# DCF_ALIM_SWITCH_RESET.net
KiCad netlist of a schematic drawn in Altium Designer
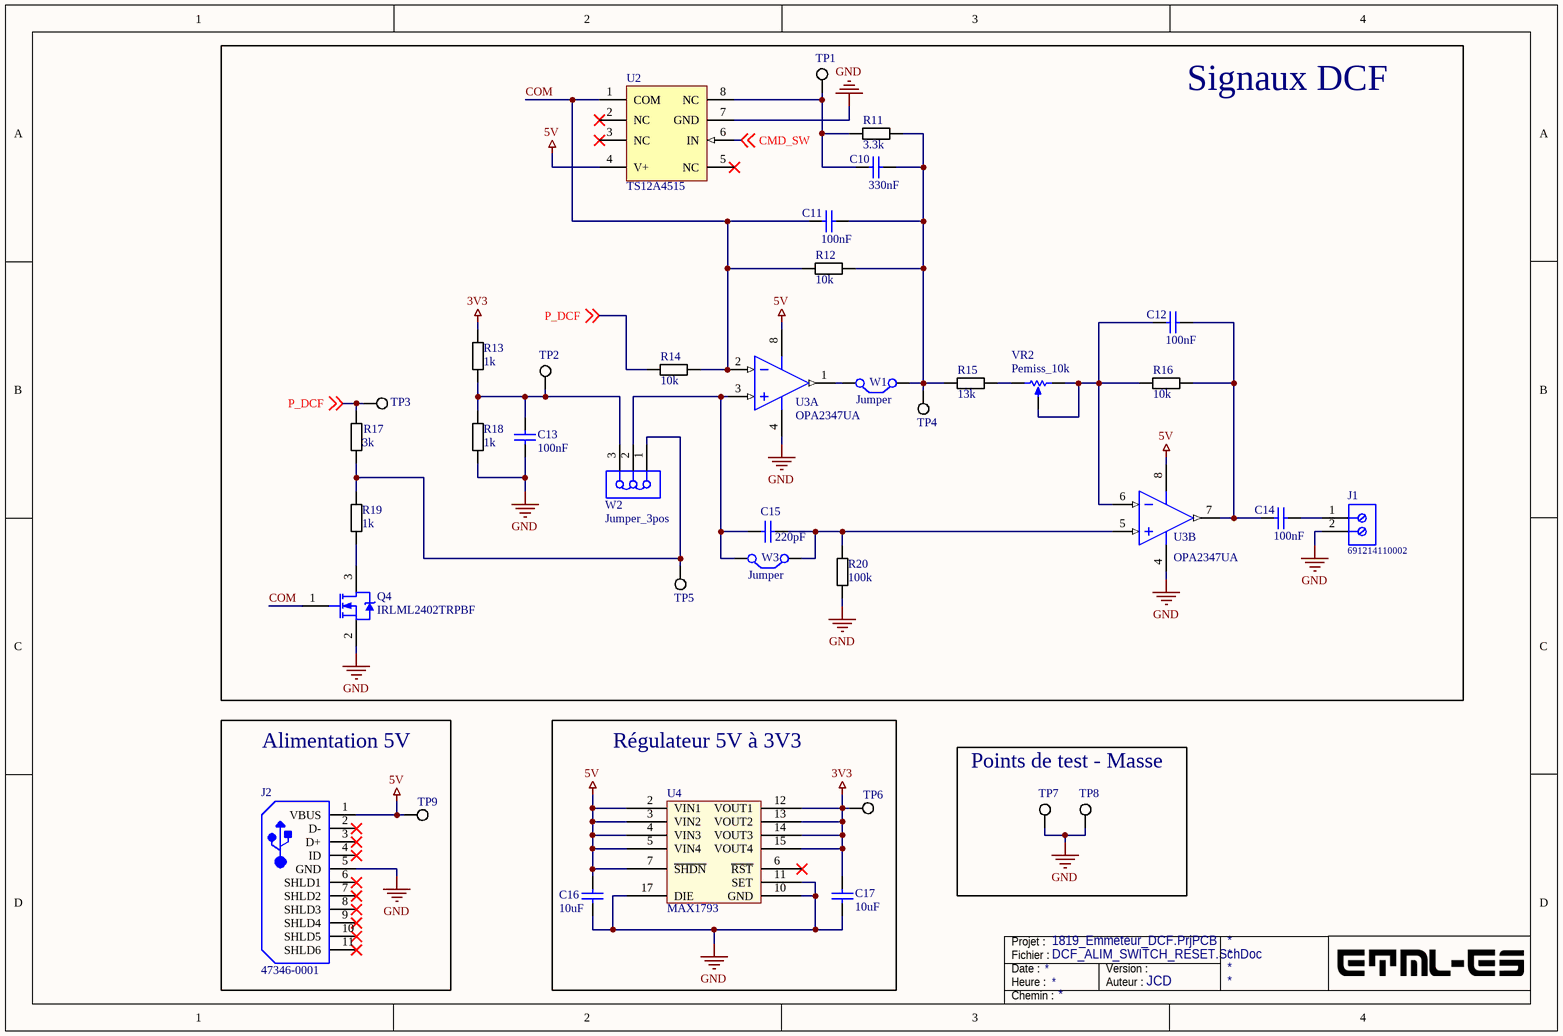
[diagram p0: DCF_ALIM_SWITCH_RESET.SchDoc]

(export (version "E")
  (design (tool "Eeschema 10.0.6"))
  (components
    (comp (ref "C10")
      (value "330nF")
      (footprint "C0805")
      (description "Capacitor")
      (fields (field (name "PUBLISHER") "Altium Limited"))
      (libsource (lib "Miscellaneous Devices") (part "Cap"))
    )
    (comp (ref "C11")
      (value "100nF")
      (footprint "C0805")
      (description "Capacitor")
      (fields (field (name "PUBLISHER") "Altium Limited"))
      (libsource (lib "Miscellaneous Devices") (part "Cap"))
    )
    (comp (ref "C12")
      (value "100nF")
      (footprint "C0805")
      (description "Capacitor")
      (fields (field (name "PUBLISHER") "Altium Limited"))
      (libsource (lib "Miscellaneous Devices") (part "Cap"))
    )
    (comp (ref "C13")
      (value "100nF")
      (footprint "C0805")
      (description "Capacitor")
      (fields (field (name "PUBLISHER") "Altium Limited"))
      (libsource (lib "Miscellaneous Devices") (part "Cap"))
    )
    (comp (ref "C14")
      (value "100nF")
      (footprint "C0805")
      (description "Capacitor")
      (fields (field (name "PUBLISHER") "Altium Limited"))
      (libsource (lib "Miscellaneous Devices") (part "Cap"))
    )
    (comp (ref "C15")
      (value "220pF")
      (footprint "C0805")
      (description "Capacitor")
      (fields (field (name "PUBLISHER") "Altium Limited"))
      (libsource (lib "Miscellaneous Devices") (part "Cap"))
    )
    (comp (ref "C16")
      (value "10uF")
      (footprint "C0805")
      (description "Capacitor")
      (fields (field (name "PUBLISHER") "Altium Limited"))
      (libsource (lib "Miscellaneous Devices") (part "Cap"))
    )
    (comp (ref "C17")
      (value "10uF")
      (footprint "C0805")
      (description "Capacitor")
      (fields (field (name "PUBLISHER") "Altium Limited"))
      (libsource (lib "Miscellaneous Devices") (part "Cap"))
    )
    (comp (ref "J1")
      (value "691214110002")
      (footprint "691214110002")
      (description "Serie 2141 - 3.50 mm Horizontal Entry Modular with Rising Cage Clamp WR-TBL, 2 pin")
      (fields (field (name "PUBLISHER") "Wurth Elektronik"))
      (libsource (lib "ALTIUM-RISING_CAGE_CLAMP_CONTBL2-rev18b") (part "691214110002"))
    )
    (comp (ref "J2")
      (value "47346-0001")
      (footprint "MOLX-47346-0001-5_V")
      (description "Micro-USB B Receptacle with Flange, -30 to 85 degC, 5-Pin SMD, RoHS, Tape and Reel")
      (fields (field (name "MANUFACTURER") "Molex"))
      (libsource (lib "Altium Content Vault") (part "MOLX-47346-0001-5"))
    )
    (comp (ref "Q4")
      (value "IRLML2402TRPBF")
      (footprint "INTR-IRLML2402TRPBF-3_V")
      (description "HEXFET(R) Power MOSFET, N-Channel, 20 V, 1.2 A, 3-Pin SOT-23, RoHS, Tape and Reel")
      (fields (field (name "MANUFACTURER") "International Rectifier"))
      (libsource (lib "Altium Content Vault") (part "NEMOS-GSD-3_A"))
    )
    (comp (ref "R11")
      (value "3.3k")
      (footprint "RESC0805(2012)_L")
      (libsource (lib "LibComposant1819") (part "Resistance"))
    )
    (comp (ref "R12")
      (value "10k")
      (footprint "RESC0805(2012)_L")
      (libsource (lib "LibComposant1819") (part "Resistance"))
    )
    (comp (ref "R13") (value "1k") (footprint "RESC0805(2012)_L") (libsource (lib "") (part "Resistance_1")))
    (comp (ref "R14")
      (value "10k")
      (footprint "RESC0805(2012)_L")
      (libsource (lib "LibComposant1819") (part "Resistance"))
    )
    (comp (ref "R15")
      (value "13k")
      (footprint "RESC0805(2012)_L")
      (libsource (lib "LibComposant1819") (part "Resistance"))
    )
    (comp (ref "R16")
      (value "10k")
      (footprint "RESC0805(2012)_L")
      (libsource (lib "LibComposant1819") (part "Resistance"))
    )
    (comp (ref "R17") (value "3k") (footprint "RESC0805(2012)_L") (libsource (lib "") (part "Resistance_1")))
    (comp (ref "R18") (value "1k") (footprint "RESC0805(2012)_L") (libsource (lib "") (part "Resistance_1")))
    (comp (ref "R19") (value "1k") (footprint "RESC0805(2012)_L") (libsource (lib "") (part "Resistance_1")))
    (comp (ref "R20")
      (value "100k")
      (footprint "RESC0805(2012)_L")
      (libsource (lib "") (part "Resistance_1"))
    )
    (comp (ref "TP1")
      (value "5019")
      (footprint "KSTN-5019_V")
      (description "Test Point, 1 Position SMD, RoHS, Tape and Reel")
      (libsource (lib "Altium Content Vault") (part "TESTPOINT_WHITE"))
    )
    (comp (ref "TP2")
      (value "5019")
      (footprint "KSTN-5019_V")
      (description "Test Point, 1 Position SMD, RoHS, Tape and Reel")
      (libsource (lib "Altium Content Vault") (part "TESTPOINT_WHITE"))
    )
    (comp (ref "TP3")
      (value "5019")
      (footprint "KSTN-5019_V")
      (description "Test Point, 1 Position SMD, RoHS, Tape and Reel")
      (libsource (lib "Altium Content Vault") (part "TESTPOINT_WHITE"))
    )
    (comp (ref "TP4")
      (value "5019")
      (footprint "KSTN-5019_V")
      (description "Test Point, 1 Position SMD, RoHS, Tape and Reel")
      (libsource (lib "Altium Content Vault") (part "TESTPOINT_WHITE"))
    )
    (comp (ref "TP5")
      (value "5019")
      (footprint "KSTN-5019_V")
      (description "Test Point, 1 Position SMD, RoHS, Tape and Reel")
      (libsource (lib "Altium Content Vault") (part "TESTPOINT_WHITE"))
    )
    (comp (ref "TP6")
      (value "5019")
      (footprint "KSTN-5019_V")
      (description "Test Point, 1 Position SMD, RoHS, Tape and Reel")
      (libsource (lib "Altium Content Vault") (part "TESTPOINT_WHITE"))
    )
    (comp (ref "TP7")
      (value "5019")
      (footprint "KSTN-5019_V")
      (description "Test Point, 1 Position SMD, RoHS, Tape and Reel")
      (libsource (lib "Altium Content Vault") (part "TESTPOINT_WHITE"))
    )
    (comp (ref "TP8")
      (value "5019")
      (footprint "KSTN-5019_V")
      (description "Test Point, 1 Position SMD, RoHS, Tape and Reel")
      (libsource (lib "Altium Content Vault") (part "TESTPOINT_WHITE"))
    )
    (comp (ref "TP9")
      (value "5019")
      (footprint "KSTN-5019_V")
      (description "Test Point, 1 Position SMD, RoHS, Tape and Reel")
      (libsource (lib "Altium Content Vault") (part "TESTPOINT_WHITE"))
    )
    (comp (ref "U2")
      (value "TS12A4515")
      (footprint "TI-D8_L")
      (fields (field (name "MANUFACTURER") "Texas Instruments") (field (name "PARTNUMBER") "TS12A4516D"))
      (libsource (lib "LibComposant1819") (part "TS12A4515"))
    )
    (comp (ref "U3")
      (value "OPA2347UA")
      (footprint "D0008A_M")
      (fields (field (name "MANUFACTURER") "Texas Instruments"))
      (libsource (lib "Altium Content Vault") (part "TI-OPA-8_2"))
    )
    (comp (ref "U4")
      (value "MAX1793")
      (footprint "MAX1793")
      (libsource (lib "LibComposant1819") (part "MAX1793"))
    )
    (comp (ref "VR2")
      (value "Pemiss_10k")
      (footprint "BOUR-3362P")
      (description "Square Trimpot(R) Trimming Potentiometer, 10 KOhm, 300 V, -55 to 125 degC, 3-Pin THD, RoHS, Tube")
      (fields (field (name "TOLERANCE") "1%"))
      (libsource (lib "Altium Content Vault") (part "RES-POT-3"))
    )
    (comp (ref "W1")
      (value "Jumper")
      (footprint "Jumper_2POS")
      (description "Jumper Wire")
      (fields (field (name "PUBLISHER") "Altium Limited"))
      (libsource (lib "Miscellaneous Devices") (part "Jumper"))
    )
    (comp (ref "W2")
      (value "Jumper_3pos")
      (footprint "Jumper_3pos")
      (libsource (lib "LibComposant1819") (part "Jumper_3pos"))
    )
    (comp (ref "W3")
      (value "Jumper")
      (footprint "Jumper_2POS")
      (description "Jumper Wire")
      (fields (field (name "PUBLISHER") "Altium Limited"))
      (libsource (lib "Miscellaneous Devices") (part "Jumper"))
    )
  )
  (nets
    (net (code "1") (name "/COM") (class "Default")
      (node (ref "C11") (pin "2") (pinfunction "2_2") (pintype "passive"))
      (node (ref "Q4") (pin "1") (pinfunction "G_1") (pintype "passive"))
      (node (ref "R12") (pin "1") (pinfunction "1_1") (pintype "passive"))
      (node (ref "R14") (pin "2") (pinfunction "2_2") (pintype "passive"))
      (node (ref "U2") (pin "1") (pinfunction "COM_1") (pintype "passive"))
      (node (ref "U3") (pin "2") (pinfunction "IN_A-_2") (pintype "input"))
    )
    (net (code "2") (name "3V3") (class "Default")
      (node (ref "C17") (pin "2") (pinfunction "2_2") (pintype "passive"))
      (node (ref "R13") (pin "1") (pinfunction "1_1") (pintype "passive"))
      (node (ref "TP6") (pin "1") (pinfunction "1_1") (pintype "passive"))
      (node (ref "U4") (pin "12") (pinfunction "VOUT1_12") (pintype "passive"))
      (node (ref "U4") (pin "13") (pinfunction "VOUT2_13") (pintype "passive"))
      (node (ref "U4") (pin "14") (pinfunction "VOUT3_14") (pintype "passive"))
      (node (ref "U4") (pin "15") (pinfunction "VOUT4_15") (pintype "passive"))
    )
    (net (code "3") (name "5V") (class "Default")
      (node (ref "C16") (pin "2") (pinfunction "2_2") (pintype "passive"))
      (node (ref "J2") (pin "1") (pinfunction "VBUS_1") (pintype "passive"))
      (node (ref "TP9") (pin "1") (pinfunction "1_1") (pintype "passive"))
      (node (ref "U2") (pin "4") (pinfunction "V+_4") (pintype "power_in"))
      (node (ref "U3") (pin "8") (pinfunction "V+_8") (pintype "power_in"))
      (node (ref "U4") (pin "2") (pinfunction "VIN1_2") (pintype "passive"))
      (node (ref "U4") (pin "3") (pinfunction "VIN2_3") (pintype "passive"))
      (node (ref "U4") (pin "4") (pinfunction "VIN3_4") (pintype "passive"))
      (node (ref "U4") (pin "5") (pinfunction "VIN4_5") (pintype "passive"))
      (node (ref "U4") (pin "7") (pinfunction "~{SHDN}_7") (pintype "passive"))
    )
    (net (code "4") (name "CMD_SW") (class "Default")
      (node (ref "U2") (pin "6") (pinfunction "IN_6") (pintype "input"))
    )
    (net (code "5") (name "GND") (class "Default")
      (node (ref "C13") (pin "1") (pinfunction "1_1") (pintype "passive"))
      (node (ref "C16") (pin "1") (pinfunction "1_1") (pintype "passive"))
      (node (ref "C17") (pin "1") (pinfunction "1_1") (pintype "passive"))
      (node (ref "J1") (pin "2") (pinfunction "2_2") (pintype "passive"))
      (node (ref "J2") (pin "5") (pinfunction "GND_5") (pintype "passive"))
      (node (ref "Q4") (pin "2") (pinfunction "S_2") (pintype "passive"))
      (node (ref "R18") (pin "2") (pinfunction "2_2") (pintype "passive"))
      (node (ref "R20") (pin "2") (pinfunction "2_2") (pintype "passive"))
      (node (ref "TP7") (pin "1") (pinfunction "1_1") (pintype "passive"))
      (node (ref "TP8") (pin "1") (pinfunction "1_1") (pintype "passive"))
      (node (ref "U2") (pin "7") (pinfunction "GND_7") (pintype "power_in"))
      (node (ref "U3") (pin "4") (pinfunction "V-_4") (pintype "power_in"))
      (node (ref "U4") (pin "10") (pinfunction "GND_10") (pintype "passive"))
      (node (ref "U4") (pin "11") (pinfunction "SET_11") (pintype "passive"))
      (node (ref "U4") (pin "17") (pinfunction "DIE_17") (pintype "passive"))
    )
    (net (code "6") (name "Net-(C10-Pad2)") (class "Default")
      (node (ref "C10") (pin "2") (pinfunction "2_2") (pintype "passive"))
      (node (ref "R11") (pin "1") (pinfunction "1_1") (pintype "passive"))
      (node (ref "TP1") (pin "1") (pinfunction "1_1") (pintype "passive"))
      (node (ref "U2") (pin "8") (pinfunction "NC_8") (pintype "passive"))
    )
    (net (code "7") (name "Net-(C13-Pad2)") (class "Default")
      (node (ref "C13") (pin "2") (pinfunction "2_2") (pintype "passive"))
      (node (ref "R13") (pin "2") (pinfunction "2_2") (pintype "passive"))
      (node (ref "R18") (pin "1") (pinfunction "1_1") (pintype "passive"))
      (node (ref "TP2") (pin "1") (pinfunction "1_1") (pintype "passive"))
      (node (ref "W2") (pin "3") (pinfunction "3_3") (pintype "passive"))
    )
    (net (code "8") (name "Net-(C14-Pad1)") (class "Default")
      (node (ref "C14") (pin "1") (pinfunction "1_1") (pintype "passive"))
      (node (ref "J1") (pin "1") (pinfunction "1_1") (pintype "passive"))
    )
    (net (code "9") (name "Net-(Q4-D)") (class "Default")
      (node (ref "Q4") (pin "3") (pinfunction "D_3") (pintype "passive"))
      (node (ref "R19") (pin "2") (pinfunction "2_2") (pintype "passive"))
    )
    (net (code "10") (name "Net-(R17-Pad2)") (class "Default")
      (node (ref "R17") (pin "2") (pinfunction "2_2") (pintype "passive"))
      (node (ref "R19") (pin "1") (pinfunction "1_1") (pintype "passive"))
      (node (ref "TP5") (pin "1") (pinfunction "1_1") (pintype "passive"))
      (node (ref "W2") (pin "1") (pinfunction "1_1") (pintype "passive"))
    )
    (net (code "11") (name "Net-(U3A-IN_A+)") (class "Default")
      (node (ref "C15") (pin "2") (pinfunction "2_2") (pintype "passive"))
      (node (ref "U3") (pin "3") (pinfunction "IN_A+_3") (pintype "input"))
      (node (ref "W2") (pin "2") (pinfunction "2_2") (pintype "passive"))
      (node (ref "W3") (pin "1") (pinfunction "C1_1") (pintype "passive"))
    )
    (net (code "12") (name "Net-(U3A-OUT_A)") (class "Default")
      (node (ref "U3") (pin "1") (pinfunction "OUT_A_1") (pintype "output"))
      (node (ref "W1") (pin "1") (pinfunction "C1_1") (pintype "passive"))
    )
    (net (code "13") (name "Net-(U3B-IN_B+)") (class "Default")
      (node (ref "C15") (pin "1") (pinfunction "1_1") (pintype "passive"))
      (node (ref "R20") (pin "1") (pinfunction "1_1") (pintype "passive"))
      (node (ref "U3") (pin "5") (pinfunction "IN_B+_5") (pintype "input"))
      (node (ref "W3") (pin "2") (pinfunction "C2_2") (pintype "passive"))
    )
    (net (code "14") (name "Net-(U3B-IN_B-)") (class "Default")
      (node (ref "C12") (pin "2") (pinfunction "2_2") (pintype "passive"))
      (node (ref "R16") (pin "1") (pinfunction "1_1") (pintype "passive"))
      (node (ref "U3") (pin "6") (pinfunction "IN_B-_6") (pintype "input"))
      (node (ref "VR2") (pin "2") (pinfunction "S_2") (pintype "passive"))
      (node (ref "VR2") (pin "3") (pinfunction "CW_3") (pintype "passive"))
    )
    (net (code "15") (name "Net-(U3B-OUT_B)") (class "Default")
      (node (ref "C12") (pin "1") (pinfunction "1_1") (pintype "passive"))
      (node (ref "C14") (pin "2") (pinfunction "2_2") (pintype "passive"))
      (node (ref "R16") (pin "2") (pinfunction "2_2") (pintype "passive"))
      (node (ref "U3") (pin "7") (pinfunction "OUT_B_7") (pintype "output"))
    )
    (net (code "16") (name "Net-(VR2-CCW)") (class "Default")
      (node (ref "R15") (pin "2") (pinfunction "2_2") (pintype "passive"))
      (node (ref "VR2") (pin "1") (pinfunction "CCW_1") (pintype "passive"))
    )
    (net (code "17") (name "Net-(W1-C2)") (class "Default")
      (node (ref "C10") (pin "1") (pinfunction "1_1") (pintype "passive"))
      (node (ref "C11") (pin "1") (pinfunction "1_1") (pintype "passive"))
      (node (ref "R11") (pin "2") (pinfunction "2_2") (pintype "passive"))
      (node (ref "R12") (pin "2") (pinfunction "2_2") (pintype "passive"))
      (node (ref "R15") (pin "1") (pinfunction "1_1") (pintype "passive"))
      (node (ref "TP4") (pin "1") (pinfunction "1_1") (pintype "passive"))
      (node (ref "W1") (pin "2") (pinfunction "C2_2") (pintype "passive"))
    )
    (net (code "18") (name "P_DCF") (class "Default")
      (node (ref "R14") (pin "1") (pinfunction "1_1") (pintype "passive"))
      (node (ref "R17") (pin "1") (pinfunction "1_1") (pintype "passive"))
      (node (ref "TP3") (pin "1") (pinfunction "1_1") (pintype "passive"))
    )
    (net (code "19") (name "unconnected-(J2-D+-Pad3)") (class "Default")
      (node (ref "J2") (pin "3") (pinfunction "D+_3") (pintype "passive+no_connect"))
    )
    (net (code "20") (name "unconnected-(J2-D--Pad2)") (class "Default")
      (node (ref "J2") (pin "2") (pinfunction "D-_2") (pintype "passive+no_connect"))
    )
    (net (code "21") (name "unconnected-(J2-ID-Pad4)") (class "Default")
      (node (ref "J2") (pin "4") (pinfunction "ID_4") (pintype "passive+no_connect"))
    )
    (net (code "22") (name "unconnected-(J2-SHLD1-Pad6)") (class "Default")
      (node (ref "J2") (pin "6") (pinfunction "SHLD1_6") (pintype "passive+no_connect"))
    )
    (net (code "23") (name "unconnected-(J2-SHLD2-Pad7)") (class "Default")
      (node (ref "J2") (pin "7") (pinfunction "SHLD2_7") (pintype "passive+no_connect"))
    )
    (net (code "24") (name "unconnected-(J2-SHLD3-Pad8)") (class "Default")
      (node (ref "J2") (pin "8") (pinfunction "SHLD3_8") (pintype "passive+no_connect"))
    )
    (net (code "25") (name "unconnected-(J2-SHLD4-Pad9)") (class "Default")
      (node (ref "J2") (pin "9") (pinfunction "SHLD4_9") (pintype "passive+no_connect"))
    )
    (net (code "26") (name "unconnected-(J2-SHLD5-Pad10)") (class "Default")
      (node (ref "J2") (pin "10") (pinfunction "SHLD5_10") (pintype "passive+no_connect"))
    )
    (net (code "27") (name "unconnected-(J2-SHLD6-Pad11)") (class "Default")
      (node (ref "J2") (pin "11") (pinfunction "SHLD6_11") (pintype "passive+no_connect"))
    )
    (net (code "28") (name "unconnected-(U2-NC-Pad2)") (class "Default")
      (node (ref "U2") (pin "2") (pinfunction "NC_2") (pintype "passive+no_connect"))
    )
    (net (code "29") (name "unconnected-(U2-NC-Pad3)") (class "Default")
      (node (ref "U2") (pin "3") (pinfunction "NC_3") (pintype "passive+no_connect"))
    )
    (net (code "30") (name "unconnected-(U2-NC-Pad5)") (class "Default")
      (node (ref "U2") (pin "5") (pinfunction "NC_5") (pintype "passive+no_connect"))
    )
    (net (code "31") (name "unconnected-(U4-~{RST}-Pad6)") (class "Default")
      (node (ref "U4") (pin "6") (pinfunction "~{RST}_6") (pintype "passive+no_connect"))
    )
  )
)
